# kog.net
KiCad netlist of a schematic drawn in EAGLE
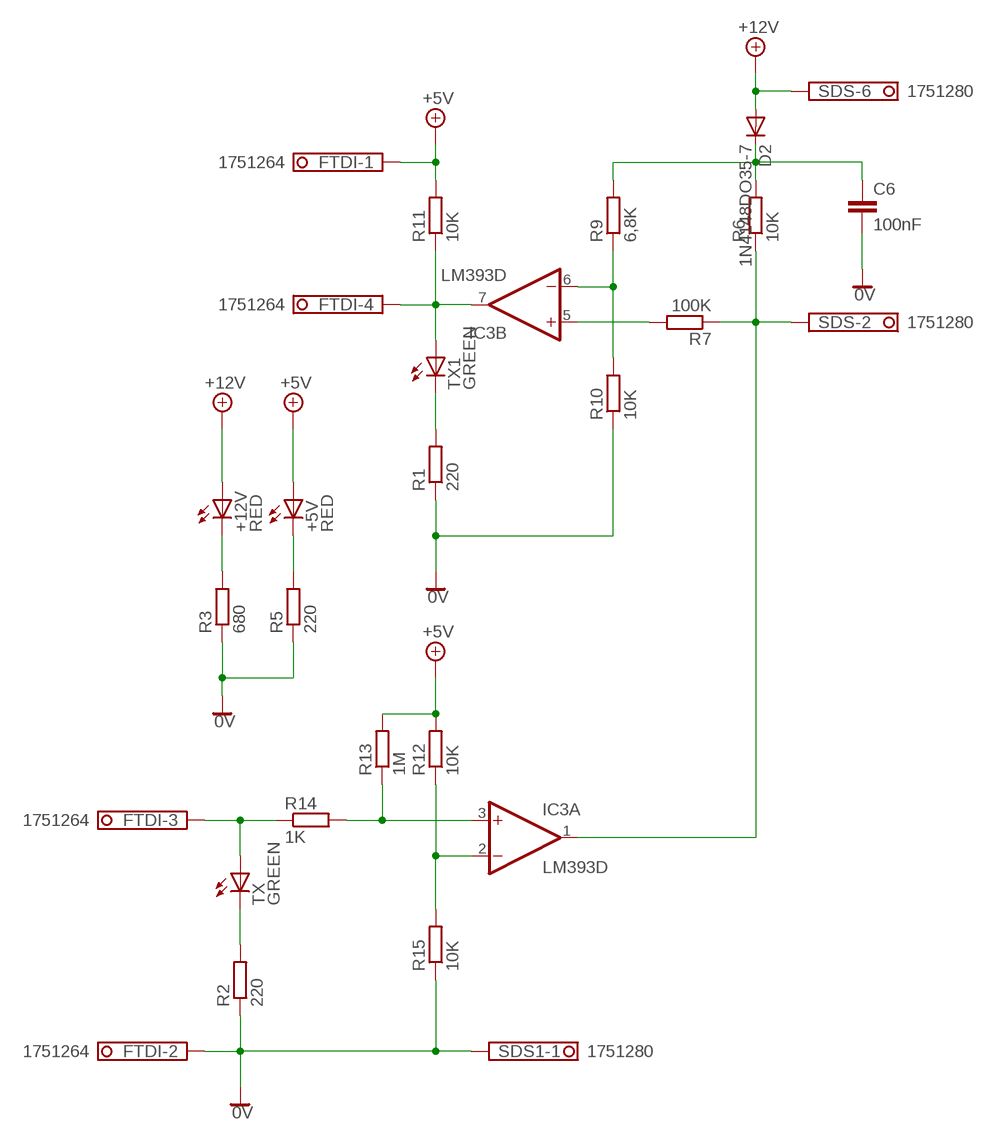
[diagram p0: schematic, sheet 1]

(export (version "E")
  (design (tool "Eeschema 10.0.6"))
  (components
    (comp (ref "+5V")
      (value "RED")
      (footprint "eagle-import:LED5MM")
      (libsource (lib "eagle-import") (part "LED5MM"))
    )
    (comp (ref "+12V")
      (value "RED")
      (footprint "eagle-import:LED5MM")
      (libsource (lib "eagle-import") (part "LED5MM"))
    )
    (comp (ref "C6")
      (value "100nF")
      (footprint "eagle-import:C025-025X050")
      (libsource (lib "eagle-import") (part "C-EU025-025X050"))
    )
    (comp (ref "D2")
      (value "1N4148DO35-7")
      (footprint "eagle-import:DO35-7")
      (libsource (lib "eagle-import") (part "1N4148DO35-7"))
    )
    (comp (ref "FTDI")
      (value "1751264")
      (footprint "eagle-import:1751264")
      (libsource (lib "eagle-import") (part "1751264"))
    )
    (comp (ref "IC3")
      (value "LM393D")
      (footprint "eagle-import:SO08")
      (libsource (lib "eagle-import") (part "LM393D"))
    )
    (comp (ref "R1")
      (value "220")
      (footprint "eagle-import:0207_10")
      (libsource (lib "eagle-import") (part "R-EU_0207/10"))
    )
    (comp (ref "R2")
      (value "220")
      (footprint "eagle-import:0207_10")
      (libsource (lib "eagle-import") (part "R-EU_0207/10"))
    )
    (comp (ref "R3")
      (value "680")
      (footprint "eagle-import:0207_10")
      (libsource (lib "eagle-import") (part "R-EU_0207/10"))
    )
    (comp (ref "R5")
      (value "220")
      (footprint "eagle-import:0207_10")
      (libsource (lib "eagle-import") (part "R-EU_0207/10"))
    )
    (comp (ref "R6")
      (value "10K")
      (footprint "eagle-import:0207_10")
      (libsource (lib "eagle-import") (part "R-EU_0207/10"))
    )
    (comp (ref "R7")
      (value "100K")
      (footprint "eagle-import:0207_10")
      (libsource (lib "eagle-import") (part "R-EU_0207/10"))
    )
    (comp (ref "R9")
      (value "6,8K")
      (footprint "eagle-import:0207_10")
      (libsource (lib "eagle-import") (part "R-EU_0207/10"))
    )
    (comp (ref "R10")
      (value "10K")
      (footprint "eagle-import:0207_10")
      (libsource (lib "eagle-import") (part "R-EU_0207/10"))
    )
    (comp (ref "R11")
      (value "10K")
      (footprint "eagle-import:0207_10")
      (libsource (lib "eagle-import") (part "R-EU_0207/10"))
    )
    (comp (ref "R12")
      (value "10K")
      (footprint "eagle-import:0207_10")
      (libsource (lib "eagle-import") (part "R-EU_0207/10"))
    )
    (comp (ref "R13")
      (value "1M")
      (footprint "eagle-import:0207_10")
      (libsource (lib "eagle-import") (part "R-EU_0207/10"))
    )
    (comp (ref "R14")
      (value "1K")
      (footprint "eagle-import:0207_10")
      (libsource (lib "eagle-import") (part "R-EU_0207/10"))
    )
    (comp (ref "R15")
      (value "10K")
      (footprint "eagle-import:0207_10")
      (libsource (lib "eagle-import") (part "R-EU_0207/10"))
    )
    (comp (ref "SDS")
      (value "1751280")
      (footprint "eagle-import:1751280")
      (libsource (lib "eagle-import") (part "1751280"))
    )
    (comp (ref "SDS1")
      (value "1751280")
      (footprint "eagle-import:1751280")
      (libsource (lib "eagle-import") (part "1751280"))
    )
    (comp (ref "TX")
      (value "GREEN")
      (footprint "eagle-import:LED5MM")
      (libsource (lib "eagle-import") (part "LED5MM"))
    )
    (comp (ref "TX1")
      (value "GREEN")
      (footprint "eagle-import:LED5MM")
      (libsource (lib "eagle-import") (part "LED5MM"))
    )
  )
  (nets
    (net (code "1") (name "+5V") (class "Default")
      (node (ref "+5V") (pin "A") (pinfunction "A_A") (pintype "passive"))
      (node (ref "FTDI") (pin "1") (pinfunction "K_1") (pintype "passive"))
      (node (ref "R11") (pin "2") (pinfunction "2_2") (pintype "passive"))
      (node (ref "R12") (pin "2") (pinfunction "2_2") (pintype "passive"))
      (node (ref "R13") (pin "2") (pinfunction "2_2") (pintype "passive"))
    )
    (net (code "2") (name "+12V") (class "Default")
      (node (ref "+12V") (pin "A") (pinfunction "A_A") (pintype "passive"))
      (node (ref "D2") (pin "A") (pinfunction "A_A") (pintype "passive"))
      (node (ref "SDS") (pin "6") (pinfunction "K_6") (pintype "passive"))
    )
    (net (code "3") (name "0V") (class "Default")
      (node (ref "C6") (pin "2") (pinfunction "2_2") (pintype "passive"))
      (node (ref "FTDI") (pin "2") (pinfunction "K_2") (pintype "passive"))
      (node (ref "R1") (pin "1") (pinfunction "1_1") (pintype "passive"))
      (node (ref "R10") (pin "1") (pinfunction "1_1") (pintype "passive"))
      (node (ref "R15") (pin "1") (pinfunction "1_1") (pintype "passive"))
      (node (ref "R2") (pin "1") (pinfunction "1_1") (pintype "passive"))
      (node (ref "R3") (pin "1") (pinfunction "1_1") (pintype "passive"))
      (node (ref "R5") (pin "1") (pinfunction "1_1") (pintype "passive"))
      (node (ref "SDS1") (pin "1") (pinfunction "K_1") (pintype "passive"))
    )
    (net (code "4") (name "Net-(+5V-C)") (class "Default")
      (node (ref "+5V") (pin "K") (pinfunction "C_K") (pintype "passive"))
      (node (ref "R5") (pin "2") (pinfunction "2_2") (pintype "passive"))
    )
    (net (code "5") (name "Net-(+12V-C)") (class "Default")
      (node (ref "+12V") (pin "K") (pinfunction "C_K") (pintype "passive"))
      (node (ref "R3") (pin "2") (pinfunction "2_2") (pintype "passive"))
    )
    (net (code "6") (name "Net-(C6-Pad1)") (class "Default")
      (node (ref "C6") (pin "1") (pinfunction "1_1") (pintype "passive"))
      (node (ref "D2") (pin "C") (pinfunction "C_C") (pintype "passive"))
      (node (ref "R6") (pin "2") (pinfunction "2_2") (pintype "passive"))
      (node (ref "R9") (pin "2") (pinfunction "2_2") (pintype "passive"))
    )
    (net (code "7") (name "Net-(FTDIC-K)") (class "Default")
      (node (ref "FTDI") (pin "3") (pinfunction "K_3") (pintype "passive"))
      (node (ref "R14") (pin "1") (pinfunction "1_1") (pintype "passive"))
      (node (ref "TX") (pin "A") (pinfunction "A_A") (pintype "passive"))
    )
    (net (code "8") (name "Net-(FTDID-K)") (class "Default")
      (node (ref "FTDI") (pin "4") (pinfunction "K_4") (pintype "passive"))
      (node (ref "IC3") (pin "7") (pinfunction "OUT_7") (pintype "output"))
      (node (ref "R11") (pin "1") (pinfunction "1_1") (pintype "passive"))
      (node (ref "TX1") (pin "A") (pinfunction "A_A") (pintype "passive"))
    )
    (net (code "9") (name "Net-(IC3A-+IN)") (class "Default")
      (node (ref "IC3") (pin "3") (pinfunction "+IN_3") (pintype "input"))
      (node (ref "R13") (pin "1") (pinfunction "1_1") (pintype "passive"))
      (node (ref "R14") (pin "2") (pinfunction "2_2") (pintype "passive"))
    )
    (net (code "10") (name "Net-(IC3A--IN)") (class "Default")
      (node (ref "IC3") (pin "2") (pinfunction "-IN_2") (pintype "input"))
      (node (ref "R12") (pin "1") (pinfunction "1_1") (pintype "passive"))
      (node (ref "R15") (pin "2") (pinfunction "2_2") (pintype "passive"))
    )
    (net (code "11") (name "Net-(IC3A-OUT)") (class "Default")
      (node (ref "IC3") (pin "1") (pinfunction "OUT_1") (pintype "output"))
      (node (ref "R6") (pin "1") (pinfunction "1_1") (pintype "passive"))
      (node (ref "R7") (pin "1") (pinfunction "1_1") (pintype "passive"))
      (node (ref "SDS") (pin "2") (pinfunction "K_2") (pintype "passive"))
    )
    (net (code "12") (name "Net-(IC3B-+IN)") (class "Default")
      (node (ref "IC3") (pin "5") (pinfunction "+IN_5") (pintype "input"))
      (node (ref "R7") (pin "2") (pinfunction "2_2") (pintype "passive"))
    )
    (net (code "13") (name "Net-(IC3B--IN)") (class "Default")
      (node (ref "IC3") (pin "6") (pinfunction "-IN_6") (pintype "input"))
      (node (ref "R10") (pin "2") (pinfunction "2_2") (pintype "passive"))
      (node (ref "R9") (pin "1") (pinfunction "1_1") (pintype "passive"))
    )
    (net (code "14") (name "Net-(TX-C)") (class "Default")
      (node (ref "R2") (pin "2") (pinfunction "2_2") (pintype "passive"))
      (node (ref "TX") (pin "K") (pinfunction "C_K") (pintype "passive"))
    )
    (net (code "15") (name "Net-(TX1-C)") (class "Default")
      (node (ref "R1") (pin "2") (pinfunction "2_2") (pintype "passive"))
      (node (ref "TX1") (pin "K") (pinfunction "C_K") (pintype "passive"))
    )
  )
)
